# Fuente_Conn.net
KiCad netlist of a schematic drawn in Altium Designer
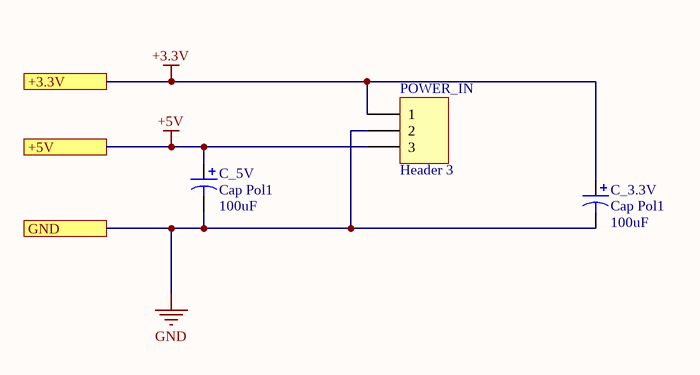
[diagram p0: Fuente_Conn.SchDoc]

(export (version "E")
  (design (tool "Eeschema 10.0.6"))
  (components
    (comp (ref "C_3.3V")
      (value "Cap Pol1")
      (footprint "CAPR5-4X5")
      (description "Polarized Capacitor (Radial)")
      (fields (field (name "ALTIUM_VALUE") "100uF") (field (name "PUBLISHER") "Altium Limited"))
      (libsource (lib "Miscellaneous Devices") (part "Cap Pol1"))
    )
    (comp (ref "C_5V")
      (value "Cap Pol1")
      (footprint "CAPR5-4X5")
      (description "Polarized Capacitor (Radial)")
      (fields (field (name "ALTIUM_VALUE") "100uF") (field (name "PUBLISHER") "Altium Limited"))
      (libsource (lib "Miscellaneous Devices") (part "Cap Pol1"))
    )
    (comp (ref "POWER_IN")
      (value "Header 3")
      (footprint "HDR1X3")
      (description "Header, 3-Pin")
      (fields (field (name "PUBLISHER") "Altium Limited"))
      (libsource (lib "Miscellaneous Connectors") (part "Header 3"))
    )
  )
  (nets
    (net (code "1") (name "+3.3V") (class "Default")
      (node (ref "C_3.3V") (pin "1") (pinfunction "1_1") (pintype "passive"))
      (node (ref "POWER_IN") (pin "1") (pinfunction "1_1") (pintype "passive"))
    )
    (net (code "2") (name "+5V") (class "Default")
      (node (ref "C_5V") (pin "1") (pinfunction "1_1") (pintype "passive"))
      (node (ref "POWER_IN") (pin "3") (pinfunction "3_3") (pintype "passive"))
    )
    (net (code "3") (name "GND") (class "Default")
      (node (ref "C_3.3V") (pin "2") (pinfunction "2_2") (pintype "passive"))
      (node (ref "C_5V") (pin "2") (pinfunction "2_2") (pintype "passive"))
      (node (ref "POWER_IN") (pin "2") (pinfunction "2_2") (pintype "passive"))
    )
  )
)
